# oldRPI_Levelshifter_LED_V02.net
KiCad netlist of a schematic drawn in EAGLE
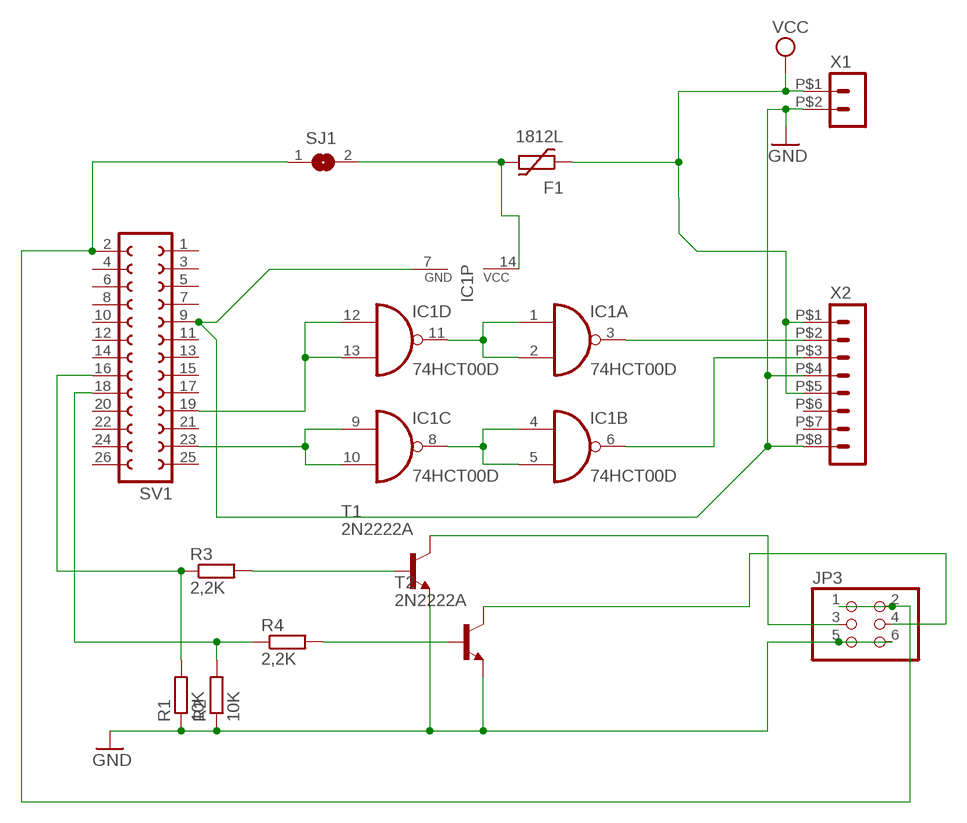
[diagram p0: schematic, sheet 1]

(export (version "E")
  (design (tool "Eeschema 10.0.6"))
  (components
    (comp (ref "F1")
      (value "1812L")
      (footprint "eagle-import:1812L")
      (libsource (lib "eagle-import") (part "1812L"))
    )
    (comp (ref "IC1")
      (value "74HCT00D")
      (footprint "eagle-import:SO14")
      (libsource (lib "eagle-import") (part "7400DHCT"))
    )
    (comp (ref "JP3")
      (value "PINHD-2X3/90")
      (footprint "eagle-import:2X03_90")
      (libsource (lib "eagle-import") (part "PINHD-2X3/90"))
    )
    (comp (ref "R1")
      (value "10K")
      (footprint "eagle-import:R1206")
      (libsource (lib "eagle-import") (part "R-EU_R1206"))
    )
    (comp (ref "R2")
      (value "10K")
      (footprint "eagle-import:R1206")
      (libsource (lib "eagle-import") (part "R-EU_R1206"))
    )
    (comp (ref "R3")
      (value "2,2K")
      (footprint "eagle-import:R1206")
      (libsource (lib "eagle-import") (part "R-EU_R1206"))
    )
    (comp (ref "R4")
      (value "2,2K")
      (footprint "eagle-import:R1206")
      (libsource (lib "eagle-import") (part "R-EU_R1206"))
    )
    (comp (ref "SJ1") (value "SJ") (footprint "eagle-import:SJ") (libsource (lib "eagle-import") (part "SJ")))
    (comp (ref "SV1")
      (value "FE13-2")
      (footprint "eagle-import:FE13-2")
      (libsource (lib "eagle-import") (part "FE13-2"))
    )
    (comp (ref "T1")
      (value "2N2222A")
      (footprint "eagle-import:SOT23-EBC")
      (libsource (lib "eagle-import") (part "-NPN-SOT23-EBC"))
    )
    (comp (ref "T2")
      (value "2N2222A")
      (footprint "eagle-import:SOT23-EBC")
      (libsource (lib "eagle-import") (part "-NPN-SOT23-EBC"))
    )
    (comp (ref "X1")
      (value "HEADER_POS2_43045-0200")
      (footprint "eagle-import:43045-0200")
      (libsource (lib "eagle-import") (part "HEADER_POS2_?43045-0200"))
    )
    (comp (ref "X2")
      (value "HEADER_POS8_43045-0800")
      (footprint "eagle-import:43045-0800")
      (libsource (lib "eagle-import") (part "HEADER_POS8_?43045-0800"))
    )
  )
  (nets
    (net (code "1") (name "GND") (class "Default")
      (node (ref "IC1") (pin "7") (pinfunction "GND_7") (pintype "power_in"))
      (node (ref "JP3") (pin "5") (pinfunction "5_5") (pintype "passive"))
      (node (ref "JP3") (pin "6") (pinfunction "6_6") (pintype "passive"))
      (node (ref "R1") (pin "1") (pinfunction "1_1") (pintype "passive"))
      (node (ref "R2") (pin "1") (pinfunction "1_1") (pintype "passive"))
      (node (ref "SV1") (pin "9") (pinfunction "9_9") (pintype "passive"))
      (node (ref "T1") (pin "E") (pinfunction "E_E") (pintype "passive"))
      (node (ref "T2") (pin "E") (pinfunction "E_E") (pintype "passive"))
      (node (ref "X1") (pin "P$2") (pinfunction "2_P$2") (pintype "passive"))
      (node (ref "X2") (pin "P$4") (pinfunction "4_P$4") (pintype "passive"))
      (node (ref "X2") (pin "P$8") (pinfunction "8_P$8") (pintype "passive"))
    )
    (net (code "2") (name "Net-(F1-2)") (class "Default")
      (node (ref "F1") (pin "P$2") (pinfunction "2_P$2") (pintype "passive"))
      (node (ref "IC1") (pin "14") (pinfunction "VCC_14") (pintype "power_in"))
      (node (ref "SJ1") (pin "2") (pinfunction "2_2") (pintype "passive"))
    )
    (net (code "3") (name "Net-(IC1A-I0)") (class "Default")
      (node (ref "IC1") (pin "1") (pinfunction "I0_1") (pintype "input"))
      (node (ref "IC1") (pin "11") (pinfunction "O_11") (pintype "output"))
      (node (ref "IC1") (pin "2") (pinfunction "I1_2") (pintype "input"))
    )
    (net (code "4") (name "Net-(IC1A-O)") (class "Default")
      (node (ref "IC1") (pin "3") (pinfunction "O_3") (pintype "output"))
      (node (ref "X2") (pin "P$2") (pinfunction "2_P$2") (pintype "passive"))
    )
    (net (code "5") (name "Net-(IC1B-I0)") (class "Default")
      (node (ref "IC1") (pin "4") (pinfunction "I0_4") (pintype "input"))
      (node (ref "IC1") (pin "5") (pinfunction "I1_5") (pintype "input"))
      (node (ref "IC1") (pin "8") (pinfunction "O_8") (pintype "output"))
    )
    (net (code "6") (name "Net-(IC1B-O)") (class "Default")
      (node (ref "IC1") (pin "6") (pinfunction "O_6") (pintype "output"))
      (node (ref "X2") (pin "P$3") (pinfunction "3_P$3") (pintype "passive"))
    )
    (net (code "7") (name "Net-(IC1C-I0)") (class "Default")
      (node (ref "IC1") (pin "10") (pinfunction "I1_10") (pintype "input"))
      (node (ref "IC1") (pin "9") (pinfunction "I0_9") (pintype "input"))
      (node (ref "SV1") (pin "23") (pinfunction "23_23") (pintype "passive"))
    )
    (net (code "8") (name "Net-(IC1D-I0)") (class "Default")
      (node (ref "IC1") (pin "12") (pinfunction "I0_12") (pintype "input"))
      (node (ref "IC1") (pin "13") (pinfunction "I1_13") (pintype "input"))
      (node (ref "SV1") (pin "19") (pinfunction "19_19") (pintype "passive"))
    )
    (net (code "9") (name "Net-(JP3-Pad1)") (class "Default")
      (node (ref "JP3") (pin "1") (pinfunction "1_1") (pintype "passive"))
      (node (ref "JP3") (pin "2") (pinfunction "2_2") (pintype "passive"))
      (node (ref "SJ1") (pin "1") (pinfunction "1_1") (pintype "passive"))
      (node (ref "SV1") (pin "2") (pinfunction "2_2") (pintype "passive"))
    )
    (net (code "10") (name "Net-(JP3-Pad3)") (class "Default")
      (node (ref "JP3") (pin "3") (pinfunction "3_3") (pintype "passive"))
      (node (ref "T1") (pin "C") (pinfunction "C_C") (pintype "passive"))
    )
    (net (code "11") (name "Net-(JP3-Pad4)") (class "Default")
      (node (ref "JP3") (pin "4") (pinfunction "4_4") (pintype "passive"))
      (node (ref "T2") (pin "C") (pinfunction "C_C") (pintype "passive"))
    )
    (net (code "12") (name "Net-(R1-Pad2)") (class "Default")
      (node (ref "R1") (pin "2") (pinfunction "2_2") (pintype "passive"))
      (node (ref "R3") (pin "1") (pinfunction "1_1") (pintype "passive"))
      (node (ref "SV1") (pin "16") (pinfunction "16_16") (pintype "passive"))
    )
    (net (code "13") (name "Net-(R2-Pad2)") (class "Default")
      (node (ref "R2") (pin "2") (pinfunction "2_2") (pintype "passive"))
      (node (ref "R4") (pin "1") (pinfunction "1_1") (pintype "passive"))
      (node (ref "SV1") (pin "18") (pinfunction "18_18") (pintype "passive"))
    )
    (net (code "14") (name "Net-(R3-Pad2)") (class "Default")
      (node (ref "R3") (pin "2") (pinfunction "2_2") (pintype "passive"))
      (node (ref "T1") (pin "B") (pinfunction "B_B") (pintype "passive"))
    )
    (net (code "15") (name "Net-(R4-Pad2)") (class "Default")
      (node (ref "R4") (pin "2") (pinfunction "2_2") (pintype "passive"))
      (node (ref "T2") (pin "B") (pinfunction "B_B") (pintype "passive"))
    )
    (net (code "16") (name "VCC") (class "Default")
      (node (ref "F1") (pin "P$1") (pinfunction "1_P$1") (pintype "passive"))
      (node (ref "X1") (pin "P$1") (pinfunction "1_P$1") (pintype "passive"))
      (node (ref "X2") (pin "P$1") (pinfunction "1_P$1") (pintype "passive"))
      (node (ref "X2") (pin "P$5") (pinfunction "5_P$5") (pintype "passive"))
    )
    (net (code "17") (name "unconnected-(SV1-Pad1)") (class "Default")
      (node (ref "SV1") (pin "1") (pinfunction "1_1") (pintype "passive"))
    )
    (net (code "18") (name "unconnected-(SV1-Pad3)") (class "Default")
      (node (ref "SV1") (pin "3") (pinfunction "3_3") (pintype "passive"))
    )
    (net (code "19") (name "unconnected-(SV1-Pad4)") (class "Default")
      (node (ref "SV1") (pin "4") (pinfunction "4_4") (pintype "passive"))
    )
    (net (code "20") (name "unconnected-(SV1-Pad5)") (class "Default")
      (node (ref "SV1") (pin "5") (pinfunction "5_5") (pintype "passive"))
    )
    (net (code "21") (name "unconnected-(SV1-Pad6)") (class "Default")
      (node (ref "SV1") (pin "6") (pinfunction "6_6") (pintype "passive"))
    )
    (net (code "22") (name "unconnected-(SV1-Pad7)") (class "Default")
      (node (ref "SV1") (pin "7") (pinfunction "7_7") (pintype "passive"))
    )
    (net (code "23") (name "unconnected-(SV1-Pad8)") (class "Default")
      (node (ref "SV1") (pin "8") (pinfunction "8_8") (pintype "passive"))
    )
    (net (code "24") (name "unconnected-(SV1-Pad10)") (class "Default")
      (node (ref "SV1") (pin "10") (pinfunction "10_10") (pintype "passive"))
    )
    (net (code "25") (name "unconnected-(SV1-Pad11)") (class "Default")
      (node (ref "SV1") (pin "11") (pinfunction "11_11") (pintype "passive"))
    )
    (net (code "26") (name "unconnected-(SV1-Pad12)") (class "Default")
      (node (ref "SV1") (pin "12") (pinfunction "12_12") (pintype "passive"))
    )
    (net (code "27") (name "unconnected-(SV1-Pad13)") (class "Default")
      (node (ref "SV1") (pin "13") (pinfunction "13_13") (pintype "passive"))
    )
    (net (code "28") (name "unconnected-(SV1-Pad14)") (class "Default")
      (node (ref "SV1") (pin "14") (pinfunction "14_14") (pintype "passive"))
    )
    (net (code "29") (name "unconnected-(SV1-Pad15)") (class "Default")
      (node (ref "SV1") (pin "15") (pinfunction "15_15") (pintype "passive"))
    )
    (net (code "30") (name "unconnected-(SV1-Pad17)") (class "Default")
      (node (ref "SV1") (pin "17") (pinfunction "17_17") (pintype "passive"))
    )
    (net (code "31") (name "unconnected-(SV1-Pad20)") (class "Default")
      (node (ref "SV1") (pin "20") (pinfunction "20_20") (pintype "passive"))
    )
    (net (code "32") (name "unconnected-(SV1-Pad21)") (class "Default")
      (node (ref "SV1") (pin "21") (pinfunction "21_21") (pintype "passive"))
    )
    (net (code "33") (name "unconnected-(SV1-Pad22)") (class "Default")
      (node (ref "SV1") (pin "22") (pinfunction "22_22") (pintype "passive"))
    )
    (net (code "34") (name "unconnected-(SV1-Pad24)") (class "Default")
      (node (ref "SV1") (pin "24") (pinfunction "24_24") (pintype "passive"))
    )
    (net (code "35") (name "unconnected-(SV1-Pad25)") (class "Default")
      (node (ref "SV1") (pin "25") (pinfunction "25_25") (pintype "passive"))
    )
    (net (code "36") (name "unconnected-(SV1-Pad26)") (class "Default")
      (node (ref "SV1") (pin "26") (pinfunction "26_26") (pintype "passive"))
    )
    (net (code "37") (name "unconnected-(X2-6-PadP$6)") (class "Default")
      (node (ref "X2") (pin "P$6") (pinfunction "6_P$6") (pintype "passive"))
    )
    (net (code "38") (name "unconnected-(X2-7-PadP$7)") (class "Default")
      (node (ref "X2") (pin "P$7") (pinfunction "7_P$7") (pintype "passive"))
    )
  )
)
